# OSO-MISC-20-014-Solar_Spike.net
KiCad netlist of a schematic drawn in EAGLE
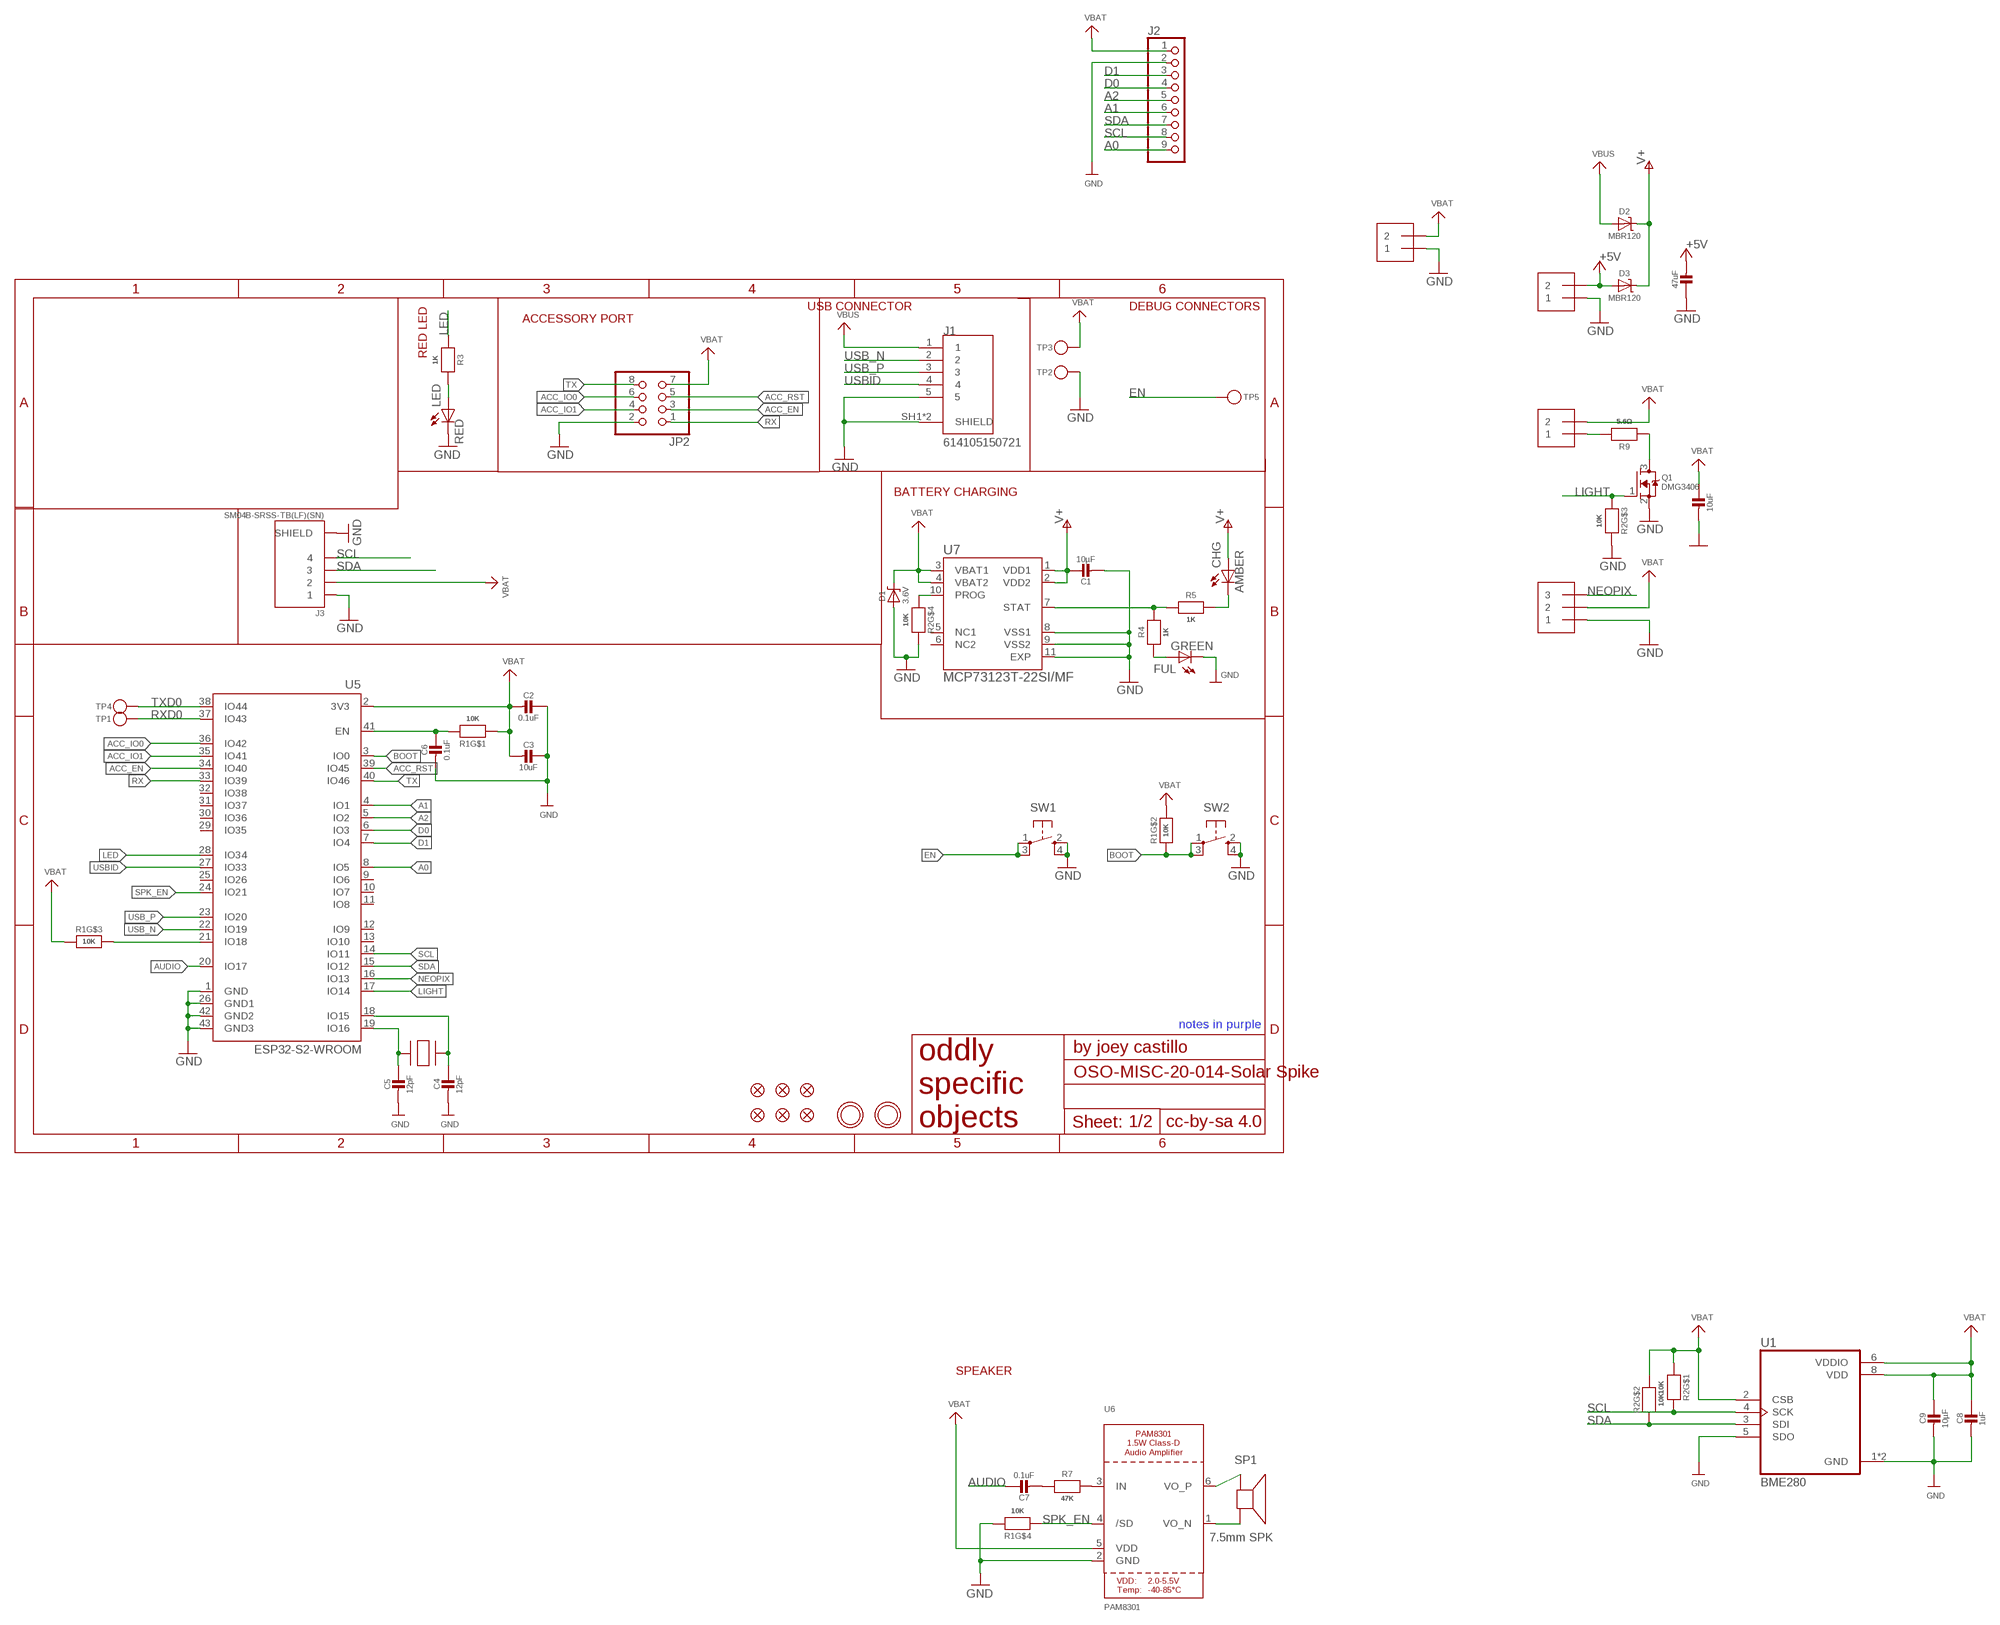
[diagram p0: schematic, sheet 1]
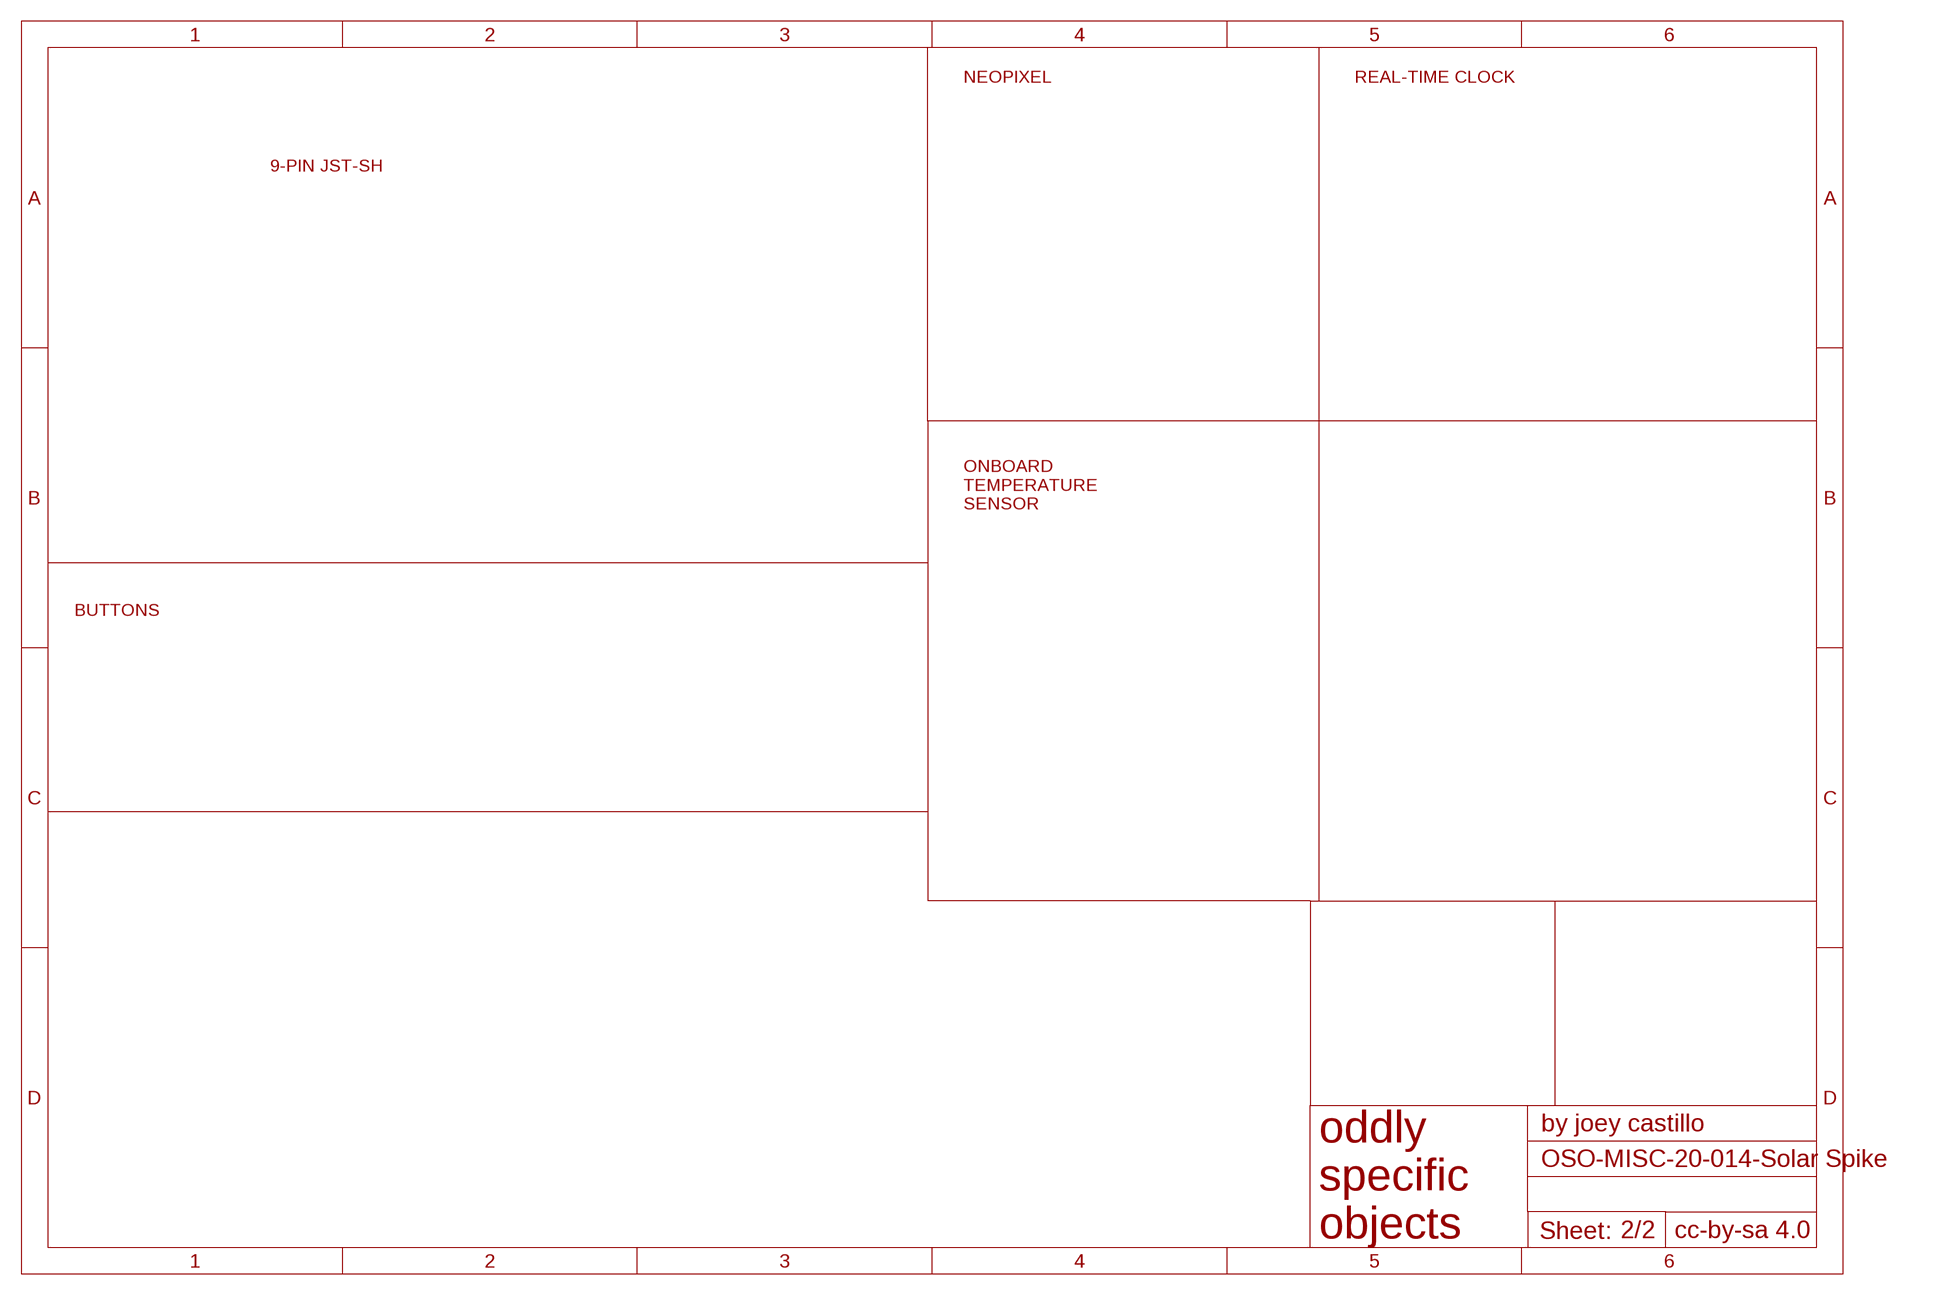
[diagram p1: schematic, sheet 2]

(export (version "E")
  (design (tool "Eeschema 10.0.6"))
  (components
    (comp (ref "BATTERY")
      (value "1X2-3.5MM")
      (footprint "eagle-import:1X2-3.5MM")
      (libsource (lib "eagle-import") (part "1X2-3.5MM"))
    )
    (comp (ref "C1")
      (value "10µF")
      (footprint "eagle-import:0805-NO")
      (libsource (lib "eagle-import") (part "CAP_CERAMIC0805-NOOUTLINE"))
    )
    (comp (ref "C2")
      (value "0.1uF")
      (footprint "eagle-import:0805-NO")
      (libsource (lib "eagle-import") (part "CAP_CERAMIC0805-NOOUTLINE"))
    )
    (comp (ref "C3")
      (value "10uF")
      (footprint "eagle-import:0805-NO")
      (libsource (lib "eagle-import") (part "CAP_CERAMIC0805-NOOUTLINE"))
    )
    (comp (ref "C4")
      (value "12pF")
      (footprint "eagle-import:0805-NO")
      (libsource (lib "eagle-import") (part "CAP_CERAMIC0805-NOOUTLINE"))
    )
    (comp (ref "C5")
      (value "12pF")
      (footprint "eagle-import:0805-NO")
      (libsource (lib "eagle-import") (part "CAP_CERAMIC0805-NOOUTLINE"))
    )
    (comp (ref "C6")
      (value "0.1uF")
      (footprint "eagle-import:0805-NO")
      (libsource (lib "eagle-import") (part "CAP_CERAMIC0805-NOOUTLINE"))
    )
    (comp (ref "C7")
      (value "0.1uF")
      (footprint "eagle-import:0805-NO")
      (libsource (lib "eagle-import") (part "CAP_CERAMIC0805-NOOUTLINE"))
    )
    (comp (ref "C8")
      (value "1uF")
      (footprint "eagle-import:0805-NO")
      (libsource (lib "eagle-import") (part "CAP_CERAMIC0805-NOOUTLINE"))
    )
    (comp (ref "C9")
      (value "10µF")
      (footprint "eagle-import:0805-NO")
      (libsource (lib "eagle-import") (part "CAP_CERAMIC0805-NOOUTLINE"))
    )
    (comp (ref "C10")
      (value "10uF")
      (footprint "eagle-import:0805-NO")
      (libsource (lib "eagle-import") (part "CAP_CERAMIC0805-NOOUTLINE"))
    )
    (comp (ref "C11")
      (value "47uF")
      (footprint "eagle-import:0805-NO")
      (libsource (lib "eagle-import") (part "CAP_CERAMIC0805-NOOUTLINE"))
    )
    (comp (ref "CHG")
      (value "AMBER")
      (footprint "eagle-import:CHIPLED_0805")
      (libsource (lib "eagle-import") (part "LEDCHIPLED_0805"))
    )
    (comp (ref "D1")
      (value "3.6V")
      (footprint "eagle-import:SOD-123")
      (libsource (lib "eagle-import") (part "DIODE-ZENERSOD123"))
    )
    (comp (ref "D2")
      (value "MBR120")
      (footprint "eagle-import:SOD-123")
      (libsource (lib "eagle-import") (part "DIODE-SCHOTTKYSOD-123"))
    )
    (comp (ref "D3")
      (value "MBR120")
      (footprint "eagle-import:SOD-123")
      (libsource (lib "eagle-import") (part "DIODE-SCHOTTKYSOD-123"))
    )
    (comp (ref "FID1")
      (value "FIDUCIAL_1MM")
      (footprint "eagle-import:FIDUCIAL_1MM")
      (libsource (lib "eagle-import") (part "FIDUCIAL_1MM"))
    )
    (comp (ref "FID2")
      (value "FIDUCIAL_1MM")
      (footprint "eagle-import:FIDUCIAL_1MM")
      (libsource (lib "eagle-import") (part "FIDUCIAL_1MM"))
    )
    (comp (ref "FID3")
      (value "FIDUCIAL_1MM")
      (footprint "eagle-import:FIDUCIAL_1MM")
      (libsource (lib "eagle-import") (part "FIDUCIAL_1MM"))
    )
    (comp (ref "FID4")
      (value "FIDUCIAL_1MM")
      (footprint "eagle-import:FIDUCIAL_1MM")
      (libsource (lib "eagle-import") (part "FIDUCIAL_1MM"))
    )
    (comp (ref "FID5")
      (value "FIDUCIAL_1MM")
      (footprint "eagle-import:FIDUCIAL_1MM")
      (libsource (lib "eagle-import") (part "FIDUCIAL_1MM"))
    )
    (comp (ref "FID6")
      (value "FIDUCIAL_1MM")
      (footprint "eagle-import:FIDUCIAL_1MM")
      (libsource (lib "eagle-import") (part "FIDUCIAL_1MM"))
    )
    (comp (ref "FUL")
      (value "GREEN")
      (footprint "eagle-import:CHIPLED_0805")
      (libsource (lib "eagle-import") (part "LEDCHIPLED_0805"))
    )
    (comp (ref "J1")
      (value "614105150721")
      (footprint "eagle-import:WURTH_614105150721")
      (fields (field (name "MF") "Wurth Electronics"))
      (libsource (lib "eagle-import") (part "614105150721"))
    )
    (comp (ref "J2")
      (value "HEADER-1X9_JSTSH_VERT")
      (footprint "eagle-import:JST_SH9_VERT")
      (libsource (lib "eagle-import") (part "HEADER-1X9_JSTSH_VERT"))
    )
    (comp (ref "J3")
      (value "SM04B-SRSS-TB(LF)(SN)")
      (footprint "eagle-import:JST_SM04B-SRSS-TB(LF)(SN)")
      (fields
        (field (name "DIGI-KEY_PART_NUMBER") "455-1804-1-ND")
        (field (name "MF") "JST Sales")
        (field (name "MP") "SM04B-SRSS-TB_LF__SN_")
      )
      (libsource (lib "eagle-import") (part "SM04B-SRSS-TB(LF)(SN)"))
    )
    (comp (ref "JP2")
      (value "PINHD-2X4SMT")
      (footprint "eagle-import:PINHD_2X4_SMT")
      (libsource (lib "eagle-import") (part "PINHD-2X4SMT"))
    )
    (comp (ref "LED")
      (value "RED")
      (footprint "eagle-import:CHIPLED_0805")
      (libsource (lib "eagle-import") (part "LEDCHIPLED_0805"))
    )
    (comp (ref "LIGHT")
      (value "1X2-3.5MM")
      (footprint "eagle-import:1X2-3.5MM")
      (libsource (lib "eagle-import") (part "1X2-3.5MM"))
    )
    (comp (ref "NEOPIX")
      (value "1X3")
      (footprint "eagle-import:1X3-3.5MM")
      (libsource (lib "eagle-import") (part "1X3"))
    )
    (comp (ref "Q1")
      (value "DMG3406")
      (footprint "eagle-import:SOT23-WIDE")
      (libsource (lib "eagle-import") (part "MOSFET-NWIDE"))
    )
    (comp (ref "R1")
      (value "10K")
      (footprint "eagle-import:EXBV8V")
      (fields (field (name "MANUFACTURER_PART_NUMBER") "EXBV8V103JV"))
      (libsource (lib "eagle-import") (part "EXB-V8V103JV-GOOD"))
    )
    (comp (ref "R2")
      (value "10K")
      (footprint "eagle-import:EXBV8V")
      (fields (field (name "MANUFACTURER_PART_NUMBER") "EXBV8V103JV"))
      (libsource (lib "eagle-import") (part "EXB-V8V103JV-GOOD"))
    )
    (comp (ref "R3")
      (value "1K")
      (footprint "eagle-import:0805-NO")
      (libsource (lib "eagle-import") (part "RESISTOR0805_NOOUTLINE"))
    )
    (comp (ref "R4")
      (value "1K")
      (footprint "eagle-import:0805-NO")
      (libsource (lib "eagle-import") (part "RESISTOR0805_NOOUTLINE"))
    )
    (comp (ref "R5")
      (value "1K")
      (footprint "eagle-import:0805-NO")
      (libsource (lib "eagle-import") (part "RESISTOR0805_NOOUTLINE"))
    )
    (comp (ref "R7")
      (value "47K")
      (footprint "eagle-import:0805-NO")
      (libsource (lib "eagle-import") (part "RESISTOR0805_NOOUTLINE"))
    )
    (comp (ref "R9")
      (value "5.6Ω")
      (footprint "eagle-import:0805-NO")
      (libsource (lib "eagle-import") (part "RESISTOR0805_NOOUTLINE"))
    )
    (comp (ref "SOLAR")
      (value "1X2-3.5MM")
      (footprint "eagle-import:1X2-3.5MM")
      (libsource (lib "eagle-import") (part "1X2-3.5MM"))
    )
    (comp (ref "SP1")
      (value "7.5mm SPK")
      (footprint "eagle-import:BUZZER_SMT_5MM")
      (libsource (lib "eagle-import") (part "SPEAKER_BUZZER5MM"))
    )
    (comp (ref "SW1")
      (value "SPST_TACT-KMR2")
      (footprint "eagle-import:KMR2")
      (libsource (lib "eagle-import") (part "SPST_TACT-KMR2"))
    )
    (comp (ref "SW2")
      (value "SPST_TACT-KMR2")
      (footprint "eagle-import:KMR2")
      (libsource (lib "eagle-import") (part "SPST_TACT-KMR2"))
    )
    (comp (ref "TP1")
      (value "TESTPOINTROUND1.5MMNO")
      (footprint "eagle-import:TESTPOINT_ROUND_1.5MM_NO")
      (libsource (lib "eagle-import") (part "TESTPOINTROUND1.5MMNO"))
    )
    (comp (ref "TP2")
      (value "TESTPOINTROUND1.5MMNO")
      (footprint "eagle-import:TESTPOINT_ROUND_1.5MM_NO")
      (libsource (lib "eagle-import") (part "TESTPOINTROUND1.5MMNO"))
    )
    (comp (ref "TP3")
      (value "TESTPOINTROUND1.5MMNO")
      (footprint "eagle-import:TESTPOINT_ROUND_1.5MM_NO")
      (libsource (lib "eagle-import") (part "TESTPOINTROUND1.5MMNO"))
    )
    (comp (ref "TP4")
      (value "TESTPOINTROUND1.5MMNO")
      (footprint "eagle-import:TESTPOINT_ROUND_1.5MM_NO")
      (libsource (lib "eagle-import") (part "TESTPOINTROUND1.5MMNO"))
    )
    (comp (ref "TP5")
      (value "TESTPOINTROUND1.5MMNO")
      (footprint "eagle-import:TESTPOINT_ROUND_1.5MM_NO")
      (libsource (lib "eagle-import") (part "TESTPOINTROUND1.5MMNO"))
    )
    (comp (ref "U$1")
      (value "MOUNTINGHOLE2.5")
      (footprint "eagle-import:MOUNTINGHOLE_2.5_PLATED")
      (libsource (lib "eagle-import") (part "MOUNTINGHOLE2.5"))
    )
    (comp (ref "U$4")
      (value "MOUNTINGHOLE2.5")
      (footprint "eagle-import:MOUNTINGHOLE_2.5_PLATED")
      (libsource (lib "eagle-import") (part "MOUNTINGHOLE2.5"))
    )
    (comp (ref "U1")
      (value "BME280")
      (footprint "eagle-import:PSON65P250X250X100-8N")
      (fields (field (name "MF") "Bosch"))
      (libsource (lib "eagle-import") (part "BME280"))
    )
    (comp (ref "U5")
      (value "ESP32-S2-WROOM")
      (footprint "eagle-import:MODULE_ESP32-S2-WROOM")
      (fields (field (name "MF") "Espressif Systems"))
      (libsource (lib "eagle-import") (part "ESP32-S2-WROOM"))
    )
    (comp (ref "U6")
      (value "PAM8301")
      (footprint "eagle-import:SOT23-6")
      (libsource (lib "eagle-import") (part "PAM8301"))
    )
    (comp (ref "U7")
      (value "MCP73123T-22SI/MF")
      (footprint "eagle-import:SON50P300X300X100-11N")
      (fields (field (name "DIGI-KEY_PART_NUMBER") "MCP73123T-22SI/MFCT-ND") (field (name "MF") "Microchip"))
      (libsource (lib "eagle-import") (part "MCP73123T-22SI/MF"))
    )
    (comp (ref "X1")
      (value "XTAL-3.2X1.5")
      (footprint "eagle-import:XTAL3215")
      (libsource (lib "eagle-import") (part "XTAL-3.2X1.5"))
    )
  )
  (nets
    (net (code "1") (name "+5V") (class "Default")
      (node (ref "C11") (pin "2") (pinfunction "2_2") (pintype "passive"))
      (node (ref "D3") (pin "A") (pinfunction "A_A") (pintype "passive"))
      (node (ref "SOLAR") (pin "2") (pinfunction "2_2") (pintype "passive"))
    )
    (net (code "2") (name "A0") (class "Default")
      (node (ref "J2") (pin "9") (pinfunction "9_9") (pintype "passive"))
      (node (ref "U5") (pin "8") (pinfunction "IO5_8") (pintype "bidirectional"))
    )
    (net (code "3") (name "A1") (class "Default")
      (node (ref "J2") (pin "6") (pinfunction "6_6") (pintype "passive"))
      (node (ref "U5") (pin "4") (pinfunction "IO1_4") (pintype "bidirectional"))
    )
    (net (code "4") (name "A2") (class "Default")
      (node (ref "J2") (pin "5") (pinfunction "5_5") (pintype "passive"))
      (node (ref "U5") (pin "5") (pinfunction "IO2_5") (pintype "bidirectional"))
    )
    (net (code "5") (name "ACC_EN") (class "Default")
      (node (ref "JP2") (pin "3") (pinfunction "3_3") (pintype "passive"))
      (node (ref "U5") (pin "34") (pinfunction "IO40_34") (pintype "bidirectional"))
    )
    (net (code "6") (name "ACC_IO0") (class "Default")
      (node (ref "JP2") (pin "6") (pinfunction "6_6") (pintype "passive"))
      (node (ref "U5") (pin "36") (pinfunction "IO42_36") (pintype "bidirectional"))
    )
    (net (code "7") (name "ACC_IO1") (class "Default")
      (node (ref "JP2") (pin "4") (pinfunction "4_4") (pintype "passive"))
      (node (ref "U5") (pin "35") (pinfunction "IO41_35") (pintype "bidirectional"))
    )
    (net (code "8") (name "ACC_RST") (class "Default")
      (node (ref "JP2") (pin "5") (pinfunction "5_5") (pintype "passive"))
      (node (ref "U5") (pin "39") (pinfunction "IO45_39") (pintype "bidirectional"))
    )
    (net (code "9") (name "AUDIO") (class "Default")
      (node (ref "C7") (pin "1") (pinfunction "1_1") (pintype "passive"))
      (node (ref "U5") (pin "20") (pinfunction "IO17_20") (pintype "bidirectional"))
    )
    (net (code "10") (name "BOOT") (class "Default")
      (node (ref "R1") (pin "2") (pinfunction "1_2") (pintype "passive"))
      (node (ref "SW2") (pin "1") (pinfunction "P_1") (pintype "passive"))
      (node (ref "SW2") (pin "3") (pinfunction "P1_3") (pintype "passive"))
      (node (ref "U5") (pin "3") (pinfunction "IO0_3") (pintype "bidirectional"))
    )
    (net (code "11") (name "D0") (class "Default")
      (node (ref "J2") (pin "4") (pinfunction "4_4") (pintype "passive"))
      (node (ref "U5") (pin "6") (pinfunction "IO3_6") (pintype "bidirectional"))
    )
    (net (code "12") (name "D1") (class "Default")
      (node (ref "J2") (pin "3") (pinfunction "3_3") (pintype "passive"))
      (node (ref "U5") (pin "7") (pinfunction "IO4_7") (pintype "bidirectional"))
    )
    (net (code "13") (name "EN") (class "Default")
      (node (ref "C6") (pin "1") (pinfunction "1_1") (pintype "passive"))
      (node (ref "R1") (pin "8") (pinfunction "2_8") (pintype "passive"))
      (node (ref "SW1") (pin "1") (pinfunction "P_1") (pintype "passive"))
      (node (ref "SW1") (pin "3") (pinfunction "P1_3") (pintype "passive"))
      (node (ref "TP5") (pin "P$1") (pinfunction "P$1_P$1") (pintype "bidirectional"))
      (node (ref "U5") (pin "41") (pinfunction "EN_41") (pintype "input"))
    )
    (net (code "14") (name "GND") (class "Default")
      (node (ref "BATTERY") (pin "1") (pinfunction "1_1") (pintype "passive"))
      (node (ref "C1") (pin "2") (pinfunction "2_2") (pintype "passive"))
      (node (ref "C10") (pin "2") (pinfunction "2_2") (pintype "passive"))
      (node (ref "C11") (pin "1") (pinfunction "1_1") (pintype "passive"))
      (node (ref "C2") (pin "1") (pinfunction "1_1") (pintype "passive"))
      (node (ref "C3") (pin "1") (pinfunction "1_1") (pintype "passive"))
      (node (ref "C4") (pin "2") (pinfunction "2_2") (pintype "passive"))
      (node (ref "C5") (pin "2") (pinfunction "2_2") (pintype "passive"))
      (node (ref "C6") (pin "2") (pinfunction "2_2") (pintype "passive"))
      (node (ref "C8") (pin "2") (pinfunction "2_2") (pintype "passive"))
      (node (ref "C9") (pin "2") (pinfunction "2_2") (pintype "passive"))
      (node (ref "D1") (pin "A") (pinfunction "A_A") (pintype "passive"))
      (node (ref "FUL") (pin "C") (pinfunction "C_C") (pintype "passive"))
      (node (ref "J1") (pin "5") (pinfunction "5_5") (pintype "passive"))
      (node (ref "J1") (pin "SH1") (pinfunction "SHIELD_SH1") (pintype "passive"))
      (node (ref "J1") (pin "SH2") (pinfunction "SHIELD_SH2") (pintype "passive"))
      (node (ref "J2") (pin "2") (pinfunction "2_2") (pintype "passive"))
      (node (ref "J3") (pin "1") (pinfunction "1_1") (pintype "passive"))
      (node (ref "J3") (pin "S1") (pinfunction "SHIELD_S1") (pintype "passive"))
      (node (ref "J3") (pin "S2") (pinfunction "SHIELD_S2") (pintype "passive"))
      (node (ref "JP2") (pin "2") (pinfunction "2_2") (pintype "passive"))
      (node (ref "LED") (pin "C") (pinfunction "C_C") (pintype "passive"))
      (node (ref "NEOPIX") (pin "1") (pinfunction "1_1") (pintype "passive"))
      (node (ref "Q1") (pin "2") (pinfunction "S_2") (pintype "bidirectional"))
      (node (ref "R1") (pin "5") (pinfunction "2_5") (pintype "passive"))
      (node (ref "R2") (pin "5") (pinfunction "2_5") (pintype "passive"))
      (node (ref "R2") (pin "6") (pinfunction "2_6") (pintype "passive"))
      (node (ref "SOLAR") (pin "1") (pinfunction "1_1") (pintype "passive"))
      (node (ref "SW1") (pin "2") (pinfunction "S_2") (pintype "passive"))
      (node (ref "SW1") (pin "4") (pinfunction "S1_4") (pintype "passive"))
      (node (ref "SW2") (pin "2") (pinfunction "S_2") (pintype "passive"))
      (node (ref "SW2") (pin "4") (pinfunction "S1_4") (pintype "passive"))
      (node (ref "TP2") (pin "P$1") (pinfunction "P$1_P$1") (pintype "bidirectional"))
      (node (ref "U1") (pin "1") (pinfunction "GND_1") (pintype "power_in"))
      (node (ref "U1") (pin "5") (pinfunction "SDO_5") (pintype "bidirectional"))
      (node (ref "U1") (pin "7") (pinfunction "GND_7") (pintype "power_in"))
      (node (ref "U5") (pin "1") (pinfunction "GND_1") (pintype "power_in"))
      (node (ref "U5") (pin "26") (pinfunction "GND1_26") (pintype "power_in"))
      (node (ref "U5") (pin "42") (pinfunction "GND2_42") (pintype "power_in"))
      (node (ref "U5") (pin "43") (pinfunction "GND3_43") (pintype "power_in"))
      (node (ref "U6") (pin "2") (pinfunction "GND_2") (pintype "power_in"))
      (node (ref "U7") (pin "11") (pinfunction "EXP_11") (pintype "power_in"))
      (node (ref "U7") (pin "8") (pinfunction "VSS1_8") (pintype "power_in"))
      (node (ref "U7") (pin "9") (pinfunction "VSS2_9") (pintype "power_in"))
    )
    (net (code "15") (name "LED") (class "Default")
      (node (ref "R3") (pin "1") (pinfunction "1_1") (pintype "passive"))
      (node (ref "U5") (pin "28") (pinfunction "IO34_28") (pintype "bidirectional"))
    )
    (net (code "16") (name "LIGHT") (class "Default")
      (node (ref "Q1") (pin "1") (pinfunction "G_1") (pintype "bidirectional"))
      (node (ref "R2") (pin "3") (pinfunction "1_3") (pintype "passive"))
      (node (ref "U5") (pin "17") (pinfunction "IO14_17") (pintype "bidirectional"))
    )
    (net (code "17") (name "NEOPIX") (class "Default")
      (node (ref "NEOPIX") (pin "3") (pinfunction "3_3") (pintype "passive"))
      (node (ref "U5") (pin "16") (pinfunction "IO13_16") (pintype "bidirectional"))
    )
    (net (code "18") (name "Net-(C7-Pad2)") (class "Default")
      (node (ref "C7") (pin "2") (pinfunction "2_2") (pintype "passive"))
      (node (ref "R7") (pin "1") (pinfunction "1_1") (pintype "passive"))
    )
    (net (code "19") (name "Net-(CHG-PadC)") (class "Default")
      (node (ref "CHG") (pin "C") (pinfunction "C_C") (pintype "passive"))
      (node (ref "R5") (pin "2") (pinfunction "2_2") (pintype "passive"))
    )
    (net (code "20") (name "Net-(FUL-PadA)") (class "Default")
      (node (ref "FUL") (pin "A") (pinfunction "A_A") (pintype "passive"))
      (node (ref "R4") (pin "1") (pinfunction "1_1") (pintype "passive"))
    )
    (net (code "21") (name "Net-(LED-PadA)") (class "Default")
      (node (ref "LED") (pin "A") (pinfunction "A_A") (pintype "passive"))
      (node (ref "R3") (pin "2") (pinfunction "2_2") (pintype "passive"))
    )
    (net (code "22") (name "Net-(LIGHT-Pad1)") (class "Default")
      (node (ref "LIGHT") (pin "1") (pinfunction "1_1") (pintype "passive"))
      (node (ref "R9") (pin "2") (pinfunction "2_2") (pintype "passive"))
    )
    (net (code "23") (name "Net-(Q1-D)") (class "Default")
      (node (ref "Q1") (pin "3") (pinfunction "D_3") (pintype "bidirectional"))
      (node (ref "R9") (pin "1") (pinfunction "1_1") (pintype "passive"))
    )
    (net (code "24") (name "Net-(R1C-2)") (class "Default")
      (node (ref "R1") (pin "6") (pinfunction "2_6") (pintype "passive"))
      (node (ref "U5") (pin "21") (pinfunction "IO18_21") (pintype "bidirectional"))
    )
    (net (code "25") (name "Net-(R2D-1)") (class "Default")
      (node (ref "R2") (pin "4") (pinfunction "1_4") (pintype "passive"))
      (node (ref "U7") (pin "10") (pinfunction "PROG_10") (pintype "bidirectional"))
    )
    (net (code "26") (name "Net-(U5-IO15)") (class "Default")
      (node (ref "C4") (pin "1") (pinfunction "1_1") (pintype "passive"))
      (node (ref "U5") (pin "18") (pinfunction "IO15_18") (pintype "bidirectional"))
      (node (ref "X1") (pin "P$1") (pinfunction "P$1_P$1") (pintype "bidirectional"))
    )
    (net (code "27") (name "Net-(U5-IO16)") (class "Default")
      (node (ref "C5") (pin "1") (pinfunction "1_1") (pintype "passive"))
      (node (ref "U5") (pin "19") (pinfunction "IO16_19") (pintype "bidirectional"))
      (node (ref "X1") (pin "P$2") (pinfunction "P$2_P$2") (pintype "bidirectional"))
    )
    (net (code "28") (name "Net-(U6-IN)") (class "Default")
      (node (ref "R7") (pin "2") (pinfunction "2_2") (pintype "passive"))
      (node (ref "U6") (pin "3") (pinfunction "IN_3") (pintype "input"))
    )
    (net (code "29") (name "Net-(U6-VO_N)") (class "Default")
      (node (ref "SP1") (pin "+") (pinfunction "+_+") (pintype "passive"))
      (node (ref "U6") (pin "1") (pinfunction "VO_N_1") (pintype "output"))
    )
    (net (code "30") (name "Net-(U6-VO_P)") (class "Default")
      (node (ref "SP1") (pin "-") (pinfunction "-_-") (pintype "passive"))
      (node (ref "U6") (pin "6") (pinfunction "VO_P_6") (pintype "output"))
    )
    (net (code "31") (name "Net-(U7-STAT)") (class "Default")
      (node (ref "R4") (pin "2") (pinfunction "2_2") (pintype "passive"))
      (node (ref "R5") (pin "1") (pinfunction "1_1") (pintype "passive"))
      (node (ref "U7") (pin "7") (pinfunction "STAT_7") (pintype "output"))
    )
    (net (code "32") (name "RX") (class "Default")
      (node (ref "JP2") (pin "1") (pinfunction "1_1") (pintype "passive"))
      (node (ref "U5") (pin "33") (pinfunction "IO39_33") (pintype "bidirectional"))
    )
    (net (code "33") (name "RXD0") (class "Default")
      (node (ref "TP1") (pin "P$1") (pinfunction "P$1_P$1") (pintype "bidirectional"))
      (node (ref "U5") (pin "37") (pinfunction "IO43_37") (pintype "bidirectional"))
    )
    (net (code "34") (name "SCL") (class "Default")
      (node (ref "J2") (pin "8") (pinfunction "8_8") (pintype "passive"))
      (node (ref "J3") (pin "4") (pinfunction "4_4") (pintype "passive"))
      (node (ref "R2") (pin "8") (pinfunction "2_8") (pintype "passive"))
      (node (ref "U1") (pin "4") (pinfunction "SCK_4") (pintype "input"))
      (node (ref "U5") (pin "14") (pinfunction "IO11_14") (pintype "bidirectional"))
    )
    (net (code "35") (name "SDA") (class "Default")
      (node (ref "J2") (pin "7") (pinfunction "7_7") (pintype "passive"))
      (node (ref "J3") (pin "3") (pinfunction "3_3") (pintype "passive"))
      (node (ref "R2") (pin "7") (pinfunction "2_7") (pintype "passive"))
      (node (ref "U1") (pin "3") (pinfunction "SDI_3") (pintype "bidirectional"))
      (node (ref "U5") (pin "15") (pinfunction "IO12_15") (pintype "bidirectional"))
    )
    (net (code "36") (name "SPK_EN") (class "Default")
      (node (ref "R1") (pin "4") (pinfunction "1_4") (pintype "passive"))
      (node (ref "U5") (pin "24") (pinfunction "IO21_24") (pintype "bidirectional"))
      (node (ref "U6") (pin "4") (pinfunction "/SD_4") (pintype "input"))
    )
    (net (code "37") (name "TX") (class "Default")
      (node (ref "JP2") (pin "8") (pinfunction "8_8") (pintype "passive"))
      (node (ref "U5") (pin "40") (pinfunction "IO46_40") (pintype "bidirectional"))
    )
    (net (code "38") (name "TXD0") (class "Default")
      (node (ref "TP4") (pin "P$1") (pinfunction "P$1_P$1") (pintype "bidirectional"))
      (node (ref "U5") (pin "38") (pinfunction "IO44_38") (pintype "bidirectional"))
    )
    (net (code "39") (name "USBID") (class "Default")
      (node (ref "J1") (pin "4") (pinfunction "4_4") (pintype "passive"))
      (node (ref "U5") (pin "27") (pinfunction "IO33_27") (pintype "bidirectional"))
    )
    (net (code "40") (name "USB_N") (class "Default")
      (node (ref "J1") (pin "2") (pinfunction "2_2") (pintype "passive"))
      (node (ref "U5") (pin "22") (pinfunction "IO19_22") (pintype "bidirectional"))
    )
    (net (code "41") (name "USB_P") (class "Default")
      (node (ref "J1") (pin "3") (pinfunction "3_3") (pintype "passive"))
      (node (ref "U5") (pin "23") (pinfunction "IO20_23") (pintype "bidirectional"))
    )
    (net (code "42") (name "V+") (class "Default")
      (node (ref "C1") (pin "1") (pinfunction "1_1") (pintype "passive"))
      (node (ref "CHG") (pin "A") (pinfunction "A_A") (pintype "passive"))
      (node (ref "D2") (pin "C") (pinfunction "C_C") (pintype "passive"))
      (node (ref "D3") (pin "C") (pinfunction "C_C") (pintype "passive"))
      (node (ref "U7") (pin "1") (pinfunction "VDD1_1") (pintype "power_in"))
      (node (ref "U7") (pin "2") (pinfunction "VDD2_2") (pintype "power_in"))
    )
    (net (code "43") (name "VBAT") (class "Default")
      (node (ref "BATTERY") (pin "2") (pinfunction "2_2") (pintype "passive"))
      (node (ref "C10") (pin "1") (pinfunction "1_1") (pintype "passive"))
      (node (ref "C2") (pin "2") (pinfunction "2_2") (pintype "passive"))
      (node (ref "C3") (pin "2") (pinfunction "2_2") (pintype "passive"))
      (node (ref "C8") (pin "1") (pinfunction "1_1") (pintype "passive"))
      (node (ref "C9") (pin "1") (pinfunction "1_1") (pintype "passive"))
      (node (ref "D1") (pin "C") (pinfunction "C_C") (pintype "passive"))
      (node (ref "J2") (pin "1") (pinfunction "1_1") (pintype "passive"))
      (node (ref "J3") (pin "2") (pinfunction "2_2") (pintype "passive"))
      (node (ref "JP2") (pin "7") (pinfunction "7_7") (pintype "passive"))
      (node (ref "LIGHT") (pin "2") (pinfunction "2_2") (pintype "passive"))
      (node (ref "NEOPIX") (pin "2") (pinfunction "2_2") (pintype "passive"))
      (node (ref "R1") (pin "1") (pinfunction "1_1") (pintype "passive"))
      (node (ref "R1") (pin "3") (pinfunction "1_3") (pintype "passive"))
      (node (ref "R1") (pin "7") (pinfunction "2_7") (pintype "passive"))
      (node (ref "R2") (pin "1") (pinfunction "1_1") (pintype "passive"))
      (node (ref "R2") (pin "2") (pinfunction "1_2") (pintype "passive"))
      (node (ref "TP3") (pin "P$1") (pinfunction "P$1_P$1") (pintype "bidirectional"))
      (node (ref "U1") (pin "2") (pinfunction "CSB_2") (pintype "input"))
      (node (ref "U1") (pin "6") (pinfunction "VDDIO_6") (pintype "power_in"))
      (node (ref "U1") (pin "8") (pinfunction "VDD_8") (pintype "power_in"))
      (node (ref "U5") (pin "2") (pinfunction "3V3_2") (pintype "power_in"))
      (node (ref "U6") (pin "5") (pinfunction "VDD_5") (pintype "power_in"))
      (node (ref "U7") (pin "3") (pinfunction "VBAT1_3") (pintype "bidirectional"))
      (node (ref "U7") (pin "4") (pinfunction "VBAT2_4") (pintype "bidirectional"))
    )
    (net (code "44") (name "VBUS") (class "Default")
      (node (ref "D2") (pin "A") (pinfunction "A_A") (pintype "passive"))
      (node (ref "J1") (pin "1") (pinfunction "1_1") (pintype "passive"))
    )
    (net (code "45") (name "unconnected-(U5-IO6-Pad9)") (class "Default")
      (node (ref "U5") (pin "9") (pinfunction "IO6_9") (pintype "bidirectional"))
    )
    (net (code "46") (name "unconnected-(U5-IO7-Pad10)") (class "Default")
      (node (ref "U5") (pin "10") (pinfunction "IO7_10") (pintype "bidirectional"))
    )
    (net (code "47") (name "unconnected-(U5-IO8-Pad11)") (class "Default")
      (node (ref "U5") (pin "11") (pinfunction "IO8_11") (pintype "bidirectional"))
    )
    (net (code "48") (name "unconnected-(U5-IO9-Pad12)") (class "Default")
      (node (ref "U5") (pin "12") (pinfunction "IO9_12") (pintype "bidirectional"))
    )
    (net (code "49") (name "unconnected-(U5-IO10-Pad13)") (class "Default")
      (node (ref "U5") (pin "13") (pinfunction "IO10_13") (pintype "bidirectional"))
    )
    (net (code "50") (name "unconnected-(U5-IO26-Pad25)") (class "Default")
      (node (ref "U5") (pin "25") (pinfunction "IO26_25") (pintype "bidirectional"))
    )
    (net (code "51") (name "unconnected-(U5-IO35-Pad29)") (class "Default")
      (node (ref "U5") (pin "29") (pinfunction "IO35_29") (pintype "bidirectional"))
    )
    (net (code "52") (name "unconnected-(U5-IO36-Pad30)") (class "Default")
      (node (ref "U5") (pin "30") (pinfunction "IO36_30") (pintype "bidirectional"))
    )
    (net (code "53") (name "unconnected-(U5-IO37-Pad31)") (class "Default")
      (node (ref "U5") (pin "31") (pinfunction "IO37_31") (pintype "bidirectional"))
    )
    (net (code "54") (name "unconnected-(U5-IO38-Pad32)") (class "Default")
      (node (ref "U5") (pin "32") (pinfunction "IO38_32") (pintype "bidirectional"))
    )
    (net (code "55") (name "unconnected-(U7-NC1-Pad5)") (class "Default")
      (node (ref "U7") (pin "5") (pinfunction "NC1_5") (pintype "no_connect"))
    )
    (net (code "56") (name "unconnected-(U7-NC2-Pad6)") (class "Default")
      (node (ref "U7") (pin "6") (pinfunction "NC2_6") (pintype "no_connect"))
    )
  )
)
